# BSPD_Input.net
KiCad netlist of a schematic drawn in Altium Designer
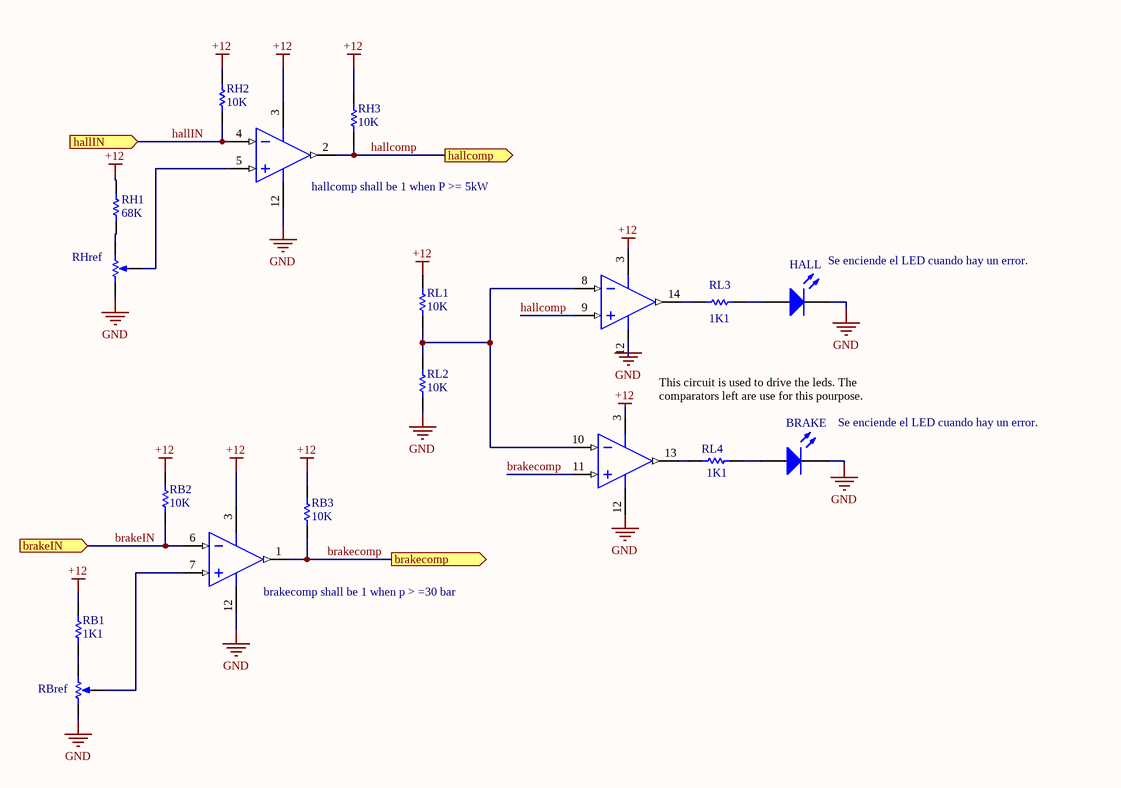
[diagram p0: BSPD_Input.SchDoc]

(export (version "E")
  (design (tool "Eeschema 10.0.6"))
  (components
    (comp (ref "BRAKE")
      (value "150120BS75000")
      (footprint "1206_A")
      (description "SMD mono-color Chip LED, WL-SMCW, Green")
      (fields (field (name "MANUFACTURER") "Wuerth Elektronik") (field (name "PARTNUMBER") "150120GS75000"))
      (libsource (lib "Altium Content Vault") (part "WE-LED_K1A2-2"))
    )
    (comp (ref "HALL")
      (value "150120BS75000")
      (footprint "1206_A")
      (description "SMD mono-color Chip LED, WL-SMCW, Red")
      (fields (field (name "PARTNUMBER") "150120RS75000") (field (name "MANUFACTURER") "Wuerth Elektronik"))
      (libsource (lib "Altium Content Vault") (part "WE-LED_K1A2-2"))
    )
    (comp (ref "RB1")
      (value "1K1")
      (footprint "RESC1206(3216)_M")
      (description "1K1 0.25W 5% 1206 (3216 Metric)  SMD")
      (fields (field (name "POWER") "0.25 W") (field (name "TOLERANCE") "5 %"))
      (libsource (lib "Altium Content Vault") (part "RES"))
    )
    (comp (ref "RB2")
      (value "10K")
      (footprint "RESC1206(3216)_M")
      (description "10K 0.25W 5% 1206 (3216 Metric)  SMD")
      (fields (field (name "POWER") "0.25 W") (field (name "TOLERANCE") "5 %"))
      (libsource (lib "Altium Content Vault") (part "RES"))
    )
    (comp (ref "RB3")
      (value "10K")
      (footprint "RESC1206(3216)_M")
      (description "10K 0.25W 5% 1206 (3216 Metric)  SMD")
      (fields (field (name "POWER") "0.25 W") (field (name "TOLERANCE") "5 %"))
      (libsource (lib "Altium Content Vault") (part "RES"))
    )
    (comp (ref "RBref")
      (value "POT Bourns 3296W 10K")
      (footprint "POT Bourns 3296W")
      (libsource (lib "LlibreriaEtech") (part "POT Bourns 3296W 10K"))
    )
    (comp (ref "RH1")
      (value "68K")
      (footprint "RESC1206(3216)_M")
      (description "68K 0.25W 5% 1206 (3216 Metric)  SMD")
      (fields (field (name "TOLERANCE") "5 %") (field (name "POWER") "0.25 W"))
      (libsource (lib "Altium Content Vault") (part "RES"))
    )
    (comp (ref "RH2")
      (value "10K")
      (footprint "RESC1206(3216)_M")
      (description "10K 0.25W 5% 1206 (3216 Metric)  SMD")
      (fields (field (name "POWER") "0.25 W") (field (name "TOLERANCE") "5 %"))
      (libsource (lib "Altium Content Vault") (part "RES"))
    )
    (comp (ref "RH3")
      (value "10K")
      (footprint "RESC1206(3216)_M")
      (description "10K 0.25W 5% 1206 (3216 Metric)  SMD")
      (fields (field (name "POWER") "0.25 W") (field (name "TOLERANCE") "5 %"))
      (libsource (lib "Altium Content Vault") (part "RES"))
    )
    (comp (ref "RHref")
      (value "POT Bourns 3296W 100K")
      (footprint "POT Bourns 3296W")
      (libsource (lib "LlibreriaEtech") (part "POT Bourns 3296W 100K"))
    )
    (comp (ref "RL1")
      (value "10K")
      (footprint "RESC1206(3216)_M")
      (description "10K 0.25W 5% 1206 (3216 Metric)  SMD")
      (fields (field (name "POWER") "0.25 W") (field (name "TOLERANCE") "5 %"))
      (libsource (lib "Altium Content Vault") (part "RES"))
    )
    (comp (ref "RL2")
      (value "10K")
      (footprint "RESC1206(3216)_M")
      (description "10K 0.25W 5% 1206 (3216 Metric)  SMD")
      (fields (field (name "POWER") "0.25 W") (field (name "TOLERANCE") "5 %"))
      (libsource (lib "Altium Content Vault") (part "RES"))
    )
    (comp (ref "RL3")
      (value "1K1")
      (footprint "RESC1206(3216)_M")
      (description "1K1 0.25W 5% 1206 (3216 Metric)  SMD")
      (fields (field (name "POWER") "0.25 W") (field (name "TOLERANCE") "5 %"))
      (libsource (lib "Altium Content Vault") (part "RES"))
    )
    (comp (ref "RL4")
      (value "1K1")
      (footprint "RESC1206(3216)_M")
      (description "1K1 0.25W 5% 1206 (3216 Metric)  SMD")
      (fields (field (name "POWER") "0.25 W") (field (name "TOLERANCE") "5 %"))
      (libsource (lib "Altium Content Vault") (part "RES"))
    )
    (comp (ref "UMP1")
      (value "LM339M")
      (footprint "D0014A_M")
      (description "Low Power Low Offset Voltage Quad Comparator, 14-pin Narrow SOIC")
      (fields (field (name "MANUFACTURER") "Texas Instruments"))
      (libsource (lib "Altium Content Vault") (part "AN-COMP-LM139-14"))
    )
  )
  (nets
    (net (code "1") (name "+12") (class "Default")
      (node (ref "RB1") (pin "2") (pinfunction "2_2") (pintype "passive"))
      (node (ref "RB2") (pin "2") (pinfunction "2_2") (pintype "passive"))
      (node (ref "RB3") (pin "2") (pinfunction "2_2") (pintype "passive"))
      (node (ref "RH1") (pin "2") (pinfunction "2_2") (pintype "passive"))
      (node (ref "RH2") (pin "2") (pinfunction "2_2") (pintype "passive"))
      (node (ref "RH3") (pin "2") (pinfunction "2_2") (pintype "passive"))
      (node (ref "RL1") (pin "2") (pinfunction "2_2") (pintype "passive"))
      (node (ref "UMP1") (pin "3") (pinfunction "V+_3") (pintype "power_in"))
    )
    (net (code "2") (name "/brakeIN") (class "Default")
      (node (ref "RB2") (pin "1") (pinfunction "1_1") (pintype "passive"))
      (node (ref "UMP1") (pin "6") (pinfunction "IN2-_6") (pintype "input"))
    )
    (net (code "3") (name "/brakecomp") (class "Default")
      (node (ref "RB3") (pin "1") (pinfunction "1_1") (pintype "passive"))
      (node (ref "UMP1") (pin "1") (pinfunction "OUT2_1") (pintype "output"))
      (node (ref "UMP1") (pin "11") (pinfunction "IN4+_11") (pintype "input"))
    )
    (net (code "4") (name "/hallIN") (class "Default")
      (node (ref "RH2") (pin "1") (pinfunction "1_1") (pintype "passive"))
      (node (ref "UMP1") (pin "4") (pinfunction "IN1-_4") (pintype "input"))
    )
    (net (code "5") (name "/hallcomp") (class "Default")
      (node (ref "RH3") (pin "1") (pinfunction "1_1") (pintype "passive"))
      (node (ref "UMP1") (pin "2") (pinfunction "OUT1_2") (pintype "output"))
      (node (ref "UMP1") (pin "9") (pinfunction "IN3+_9") (pintype "input"))
    )
    (net (code "6") (name "GND") (class "Default")
      (node (ref "BRAKE") (pin "1") (pinfunction "K_1") (pintype "passive"))
      (node (ref "HALL") (pin "1") (pinfunction "K_1") (pintype "passive"))
      (node (ref "RBref") (pin "1") (pinfunction "CCW_1") (pintype "passive"))
      (node (ref "RHref") (pin "1") (pinfunction "CCW_1") (pintype "passive"))
      (node (ref "RL2") (pin "1") (pinfunction "1_1") (pintype "passive"))
      (node (ref "UMP1") (pin "12") (pinfunction "GND_12") (pintype "power_in"))
    )
    (net (code "7") (name "Net-(BRAKE-A)") (class "Default")
      (node (ref "BRAKE") (pin "2") (pinfunction "A_2") (pintype "passive"))
      (node (ref "RL4") (pin "2") (pinfunction "2_2") (pintype "passive"))
    )
    (net (code "8") (name "Net-(HALL-A)") (class "Default")
      (node (ref "HALL") (pin "2") (pinfunction "A_2") (pintype "passive"))
      (node (ref "RL3") (pin "2") (pinfunction "2_2") (pintype "passive"))
    )
    (net (code "9") (name "Net-(RBref-CW)") (class "Default")
      (node (ref "RB1") (pin "1") (pinfunction "1_1") (pintype "passive"))
      (node (ref "RBref") (pin "3") (pinfunction "CW_3") (pintype "passive"))
    )
    (net (code "10") (name "Net-(RBref-WIPER)") (class "Default")
      (node (ref "RBref") (pin "2") (pinfunction "WIPER_2") (pintype "passive"))
      (node (ref "UMP1") (pin "7") (pinfunction "IN2+_7") (pintype "input"))
    )
    (net (code "11") (name "Net-(RHref-CW)") (class "Default")
      (node (ref "RH1") (pin "1") (pinfunction "1_1") (pintype "passive"))
      (node (ref "RHref") (pin "3") (pinfunction "CW_3") (pintype "passive"))
    )
    (net (code "12") (name "Net-(RHref-WIPER)") (class "Default")
      (node (ref "RHref") (pin "2") (pinfunction "WIPER_2") (pintype "passive"))
      (node (ref "UMP1") (pin "5") (pinfunction "IN1+_5") (pintype "input"))
    )
    (net (code "13") (name "Net-(UMP1C-IN3-)") (class "Default")
      (node (ref "RL1") (pin "1") (pinfunction "1_1") (pintype "passive"))
      (node (ref "RL2") (pin "2") (pinfunction "2_2") (pintype "passive"))
      (node (ref "UMP1") (pin "10") (pinfunction "IN4-_10") (pintype "input"))
      (node (ref "UMP1") (pin "8") (pinfunction "IN3-_8") (pintype "input"))
    )
    (net (code "14") (name "Net-(UMP1C-OUT3)") (class "Default")
      (node (ref "RL3") (pin "1") (pinfunction "1_1") (pintype "passive"))
      (node (ref "UMP1") (pin "14") (pinfunction "OUT3_14") (pintype "output"))
    )
    (net (code "15") (name "Net-(UMP1D-OUT4)") (class "Default")
      (node (ref "RL4") (pin "1") (pinfunction "1_1") (pintype "passive"))
      (node (ref "UMP1") (pin "13") (pinfunction "OUT4_13") (pintype "output"))
    )
  )
)
